# mobileCharger.net
KiCad netlist of a schematic drawn in EAGLE
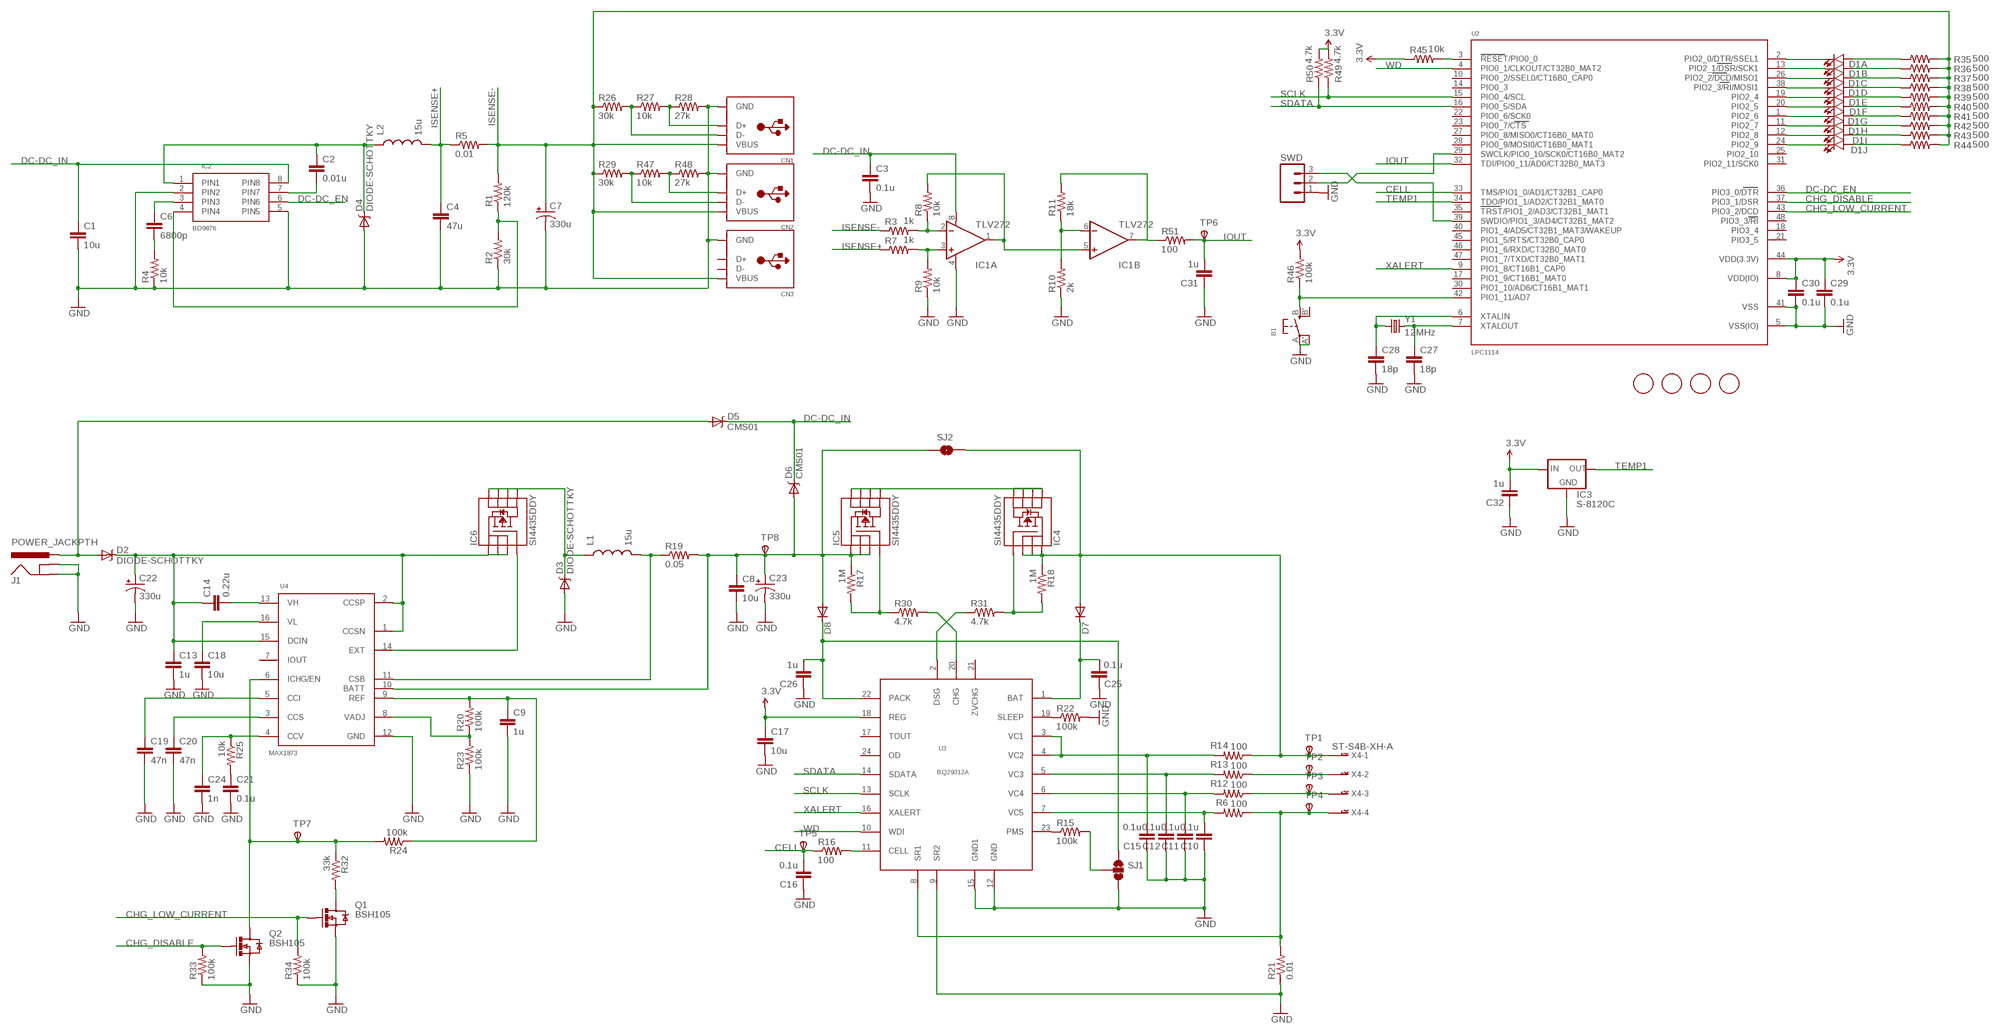
[diagram p0: schematic, sheet 1]

(export (version "E")
  (design (tool "Eeschema 10.0.6"))
  (components
    (comp (ref "B1")
      (value "SWITCH_TACT_SMT")
      (footprint "eagle-import:EVQ-Q2")
      (libsource (lib "eagle-import") (part "SWITCH_TACT_SMT"))
    )
    (comp (ref "C1")
      (value "10u")
      (footprint "eagle-import:0805")
      (libsource (lib "eagle-import") (part "SparkFun-Passives_CAP0805"))
    )
    (comp (ref "C2")
      (value "0.01u")
      (footprint "eagle-import:0603-CAP")
      (libsource (lib "eagle-import") (part "CAP0603-CAP"))
    )
    (comp (ref "C3")
      (value "0.1u")
      (footprint "eagle-import:0603-CAP")
      (libsource (lib "eagle-import") (part "CAP0603-CAP"))
    )
    (comp (ref "C4")
      (value "47u")
      (footprint "eagle-import:1206")
      (libsource (lib "eagle-import") (part "SparkFun-Passives_CAP1206"))
    )
    (comp (ref "C6")
      (value "6800p")
      (footprint "eagle-import:0603-CAP")
      (libsource (lib "eagle-import") (part "CAP0603-CAP"))
    )
    (comp (ref "C7")
      (value "330u")
      (footprint "eagle-import:CPOL-RADIAL-100UF-25V")
      (libsource (lib "eagle-import") (part "CAP_POLPTH1"))
    )
    (comp (ref "C8")
      (value "10u")
      (footprint "eagle-import:0805")
      (libsource (lib "eagle-import") (part "SparkFun-Passives_CAP0805"))
    )
    (comp (ref "C9")
      (value "1u")
      (footprint "eagle-import:0603-CAP")
      (libsource (lib "eagle-import") (part "CAP0603-CAP"))
    )
    (comp (ref "C10")
      (value "0.1u")
      (footprint "eagle-import:0603-CAP")
      (libsource (lib "eagle-import") (part "CAP0603-CAP"))
    )
    (comp (ref "C11")
      (value "0.1u")
      (footprint "eagle-import:0603-CAP")
      (libsource (lib "eagle-import") (part "CAP0603-CAP"))
    )
    (comp (ref "C12")
      (value "0.1u")
      (footprint "eagle-import:0603-CAP")
      (libsource (lib "eagle-import") (part "CAP0603-CAP"))
    )
    (comp (ref "C13")
      (value "1u")
      (footprint "eagle-import:0603-CAP")
      (libsource (lib "eagle-import") (part "CAP0603-CAP"))
    )
    (comp (ref "C14")
      (value "0.22u")
      (footprint "eagle-import:0603-CAP")
      (libsource (lib "eagle-import") (part "CAP0603-CAP"))
    )
    (comp (ref "C15")
      (value "0.1u")
      (footprint "eagle-import:0603-CAP")
      (libsource (lib "eagle-import") (part "CAP0603-CAP"))
    )
    (comp (ref "C16")
      (value "0.1u")
      (footprint "eagle-import:0603-CAP")
      (libsource (lib "eagle-import") (part "CAP0603-CAP"))
    )
    (comp (ref "C17")
      (value "10u")
      (footprint "eagle-import:0805")
      (libsource (lib "eagle-import") (part "SparkFun-Passives_CAP0805"))
    )
    (comp (ref "C18")
      (value "10u")
      (footprint "eagle-import:0805")
      (libsource (lib "eagle-import") (part "SparkFun-Passives_CAP0805"))
    )
    (comp (ref "C19")
      (value "47n")
      (footprint "eagle-import:0603-CAP")
      (libsource (lib "eagle-import") (part "CAP0603-CAP"))
    )
    (comp (ref "C20")
      (value "47n")
      (footprint "eagle-import:0603-CAP")
      (libsource (lib "eagle-import") (part "CAP0603-CAP"))
    )
    (comp (ref "C21")
      (value "0.1u")
      (footprint "eagle-import:0603-CAP")
      (libsource (lib "eagle-import") (part "CAP0603-CAP"))
    )
    (comp (ref "C22")
      (value "330u")
      (footprint "eagle-import:E3,5-8")
      (libsource (lib "eagle-import") (part "CPOL-USE3.5-8"))
    )
    (comp (ref "C23")
      (value "330u")
      (footprint "eagle-import:E3,5-8")
      (libsource (lib "eagle-import") (part "CPOL-USE3.5-8"))
    )
    (comp (ref "C24")
      (value "1n")
      (footprint "eagle-import:0603-CAP")
      (libsource (lib "eagle-import") (part "CAP0603-CAP"))
    )
    (comp (ref "C25")
      (value "0.1u")
      (footprint "eagle-import:0603-CAP")
      (libsource (lib "eagle-import") (part "CAP0603-CAP"))
    )
    (comp (ref "C26")
      (value "1u")
      (footprint "eagle-import:0603-CAP")
      (libsource (lib "eagle-import") (part "CAP0603-CAP"))
    )
    (comp (ref "C27")
      (value "18p")
      (footprint "eagle-import:0603-CAP")
      (libsource (lib "eagle-import") (part "CAP0603-CAP"))
    )
    (comp (ref "C28")
      (value "18p")
      (footprint "eagle-import:0603-CAP")
      (libsource (lib "eagle-import") (part "CAP0603-CAP"))
    )
    (comp (ref "C29")
      (value "0.1u")
      (footprint "eagle-import:0603-CAP")
      (libsource (lib "eagle-import") (part "CAP0603-CAP"))
    )
    (comp (ref "C30")
      (value "0.1u")
      (footprint "eagle-import:0603-CAP")
      (libsource (lib "eagle-import") (part "CAP0603-CAP"))
    )
    (comp (ref "C31")
      (value "1u")
      (footprint "eagle-import:0603-CAP")
      (libsource (lib "eagle-import") (part "CAP0603-CAP"))
    )
    (comp (ref "C32")
      (value "1u")
      (footprint "eagle-import:0603-CAP")
      (libsource (lib "eagle-import") (part "CAP0603-CAP"))
    )
    (comp (ref "CN1")
      (value "USB_TYPEAPTHFML")
      (footprint "eagle-import:USB_HOST-PTH")
      (libsource (lib "eagle-import") (part "USB_TYPEAPTHFML"))
    )
    (comp (ref "CN2")
      (value "USB_TYPEAPTHFML")
      (footprint "eagle-import:USB_HOST-PTH")
      (libsource (lib "eagle-import") (part "USB_TYPEAPTHFML"))
    )
    (comp (ref "CN3")
      (value "USB_TYPEAPTHFML")
      (footprint "eagle-import:USB_HOST-PTH")
      (libsource (lib "eagle-import") (part "USB_TYPEAPTHFML"))
    )
    (comp (ref "D1")
      (value "LED_BARGRAPH_10")
      (footprint "eagle-import:LED_BARGAPH_10")
      (libsource (lib "eagle-import") (part "LED_BARGRAPH_10"))
    )
    (comp (ref "D2")
      (value "DIODE-SCHOTTKY")
      (footprint "eagle-import:SOD-128")
      (libsource (lib "eagle-import") (part "DIODE-SCHOTTKY"))
    )
    (comp (ref "D3")
      (value "DIODE-SCHOTTKY")
      (footprint "eagle-import:SOD-128")
      (libsource (lib "eagle-import") (part "DIODE-SCHOTTKY"))
    )
    (comp (ref "D4")
      (value "DIODE-SCHOTTKY")
      (footprint "eagle-import:SOD-128")
      (libsource (lib "eagle-import") (part "DIODE-SCHOTTKY"))
    )
    (comp (ref "D5")
      (value "CMS01")
      (footprint "eagle-import:M-FLAT")
      (libsource (lib "eagle-import") (part "CMS01"))
    )
    (comp (ref "D6")
      (value "CMS01")
      (footprint "eagle-import:M-FLAT")
      (libsource (lib "eagle-import") (part "CMS01"))
    )
    (comp (ref "D7")
      (value "DIODESOD523")
      (footprint "eagle-import:SOD523")
      (libsource (lib "eagle-import") (part "DIODESOD523"))
    )
    (comp (ref "D8")
      (value "DIODESOD523")
      (footprint "eagle-import:SOD523")
      (libsource (lib "eagle-import") (part "DIODESOD523"))
    )
    (comp (ref "IC1")
      (value "TLV272")
      (footprint "eagle-import:SO08")
      (libsource (lib "eagle-import") (part "OPAMP-DUALU"))
    )
    (comp (ref "IC2")
      (value "BD9876")
      (footprint "eagle-import:SO08")
      (libsource (lib "eagle-import") (part "SOT8"))
    )
    (comp (ref "IC3")
      (value "S-8120C")
      (footprint "eagle-import:SC-82AB")
      (libsource (lib "eagle-import") (part "S-8120C"))
    )
    (comp (ref "IC4")
      (value "SI4435DDY")
      (footprint "eagle-import:SO08")
      (libsource (lib "eagle-import") (part "MOSFET-PCHANNEL-SOIC8SOIC8"))
    )
    (comp (ref "IC5")
      (value "SI4435DDY")
      (footprint "eagle-import:SO08")
      (libsource (lib "eagle-import") (part "MOSFET-PCHANNEL-SOIC8SOIC8"))
    )
    (comp (ref "IC6")
      (value "SI4435DDY")
      (footprint "eagle-import:SO08")
      (libsource (lib "eagle-import") (part "MOSFET-PCHANNEL-SOIC8SOIC8"))
    )
    (comp (ref "J1")
      (value "POWER_JACKPTH")
      (footprint "eagle-import:POWER_JACK_PTH")
      (libsource (lib "eagle-import") (part "POWER_JACKPTH"))
    )
    (comp (ref "L1")
      (value "15u")
      (footprint "eagle-import:CDRH125")
      (libsource (lib "eagle-import") (part "INDUCTORPWR"))
    )
    (comp (ref "L2")
      (value "15u")
      (footprint "eagle-import:CDRH125")
      (libsource (lib "eagle-import") (part "INDUCTORPWR"))
    )
    (comp (ref "Q1")
      (value "BSH105")
      (footprint "eagle-import:SOT23-3")
      (libsource (lib "eagle-import") (part "MOSFET-NCHANNELSMD"))
    )
    (comp (ref "Q2")
      (value "BSH105")
      (footprint "eagle-import:SOT23-3")
      (libsource (lib "eagle-import") (part "MOSFET-NCHANNELSMD"))
    )
    (comp (ref "R1")
      (value "120k")
      (footprint "eagle-import:0603-RES")
      (libsource (lib "eagle-import") (part "RESISTOR0603-RES"))
    )
    (comp (ref "R2")
      (value "30k")
      (footprint "eagle-import:0603-RES")
      (libsource (lib "eagle-import") (part "RESISTOR0603-RES"))
    )
    (comp (ref "R3")
      (value "1k")
      (footprint "eagle-import:0603-RES")
      (libsource (lib "eagle-import") (part "RESISTOR0603-RES"))
    )
    (comp (ref "R4")
      (value "10k")
      (footprint "eagle-import:0603-RES")
      (libsource (lib "eagle-import") (part "SparkFun-Passives_RESISTOR0603-RES"))
    )
    (comp (ref "R5")
      (value "0.01")
      (footprint "eagle-import:R1206")
      (libsource (lib "eagle-import") (part "R-US_R1206"))
    )
    (comp (ref "R6")
      (value "100")
      (footprint "eagle-import:0603-RES")
      (libsource (lib "eagle-import") (part "RESISTOR0603-RES"))
    )
    (comp (ref "R7")
      (value "1k")
      (footprint "eagle-import:0603-RES")
      (libsource (lib "eagle-import") (part "RESISTOR0603-RES"))
    )
    (comp (ref "R8")
      (value "10k")
      (footprint "eagle-import:0603-RES")
      (libsource (lib "eagle-import") (part "RESISTOR0603-RES"))
    )
    (comp (ref "R9")
      (value "10k")
      (footprint "eagle-import:0603-RES")
      (libsource (lib "eagle-import") (part "RESISTOR0603-RES"))
    )
    (comp (ref "R10")
      (value "2k")
      (footprint "eagle-import:0603-RES")
      (libsource (lib "eagle-import") (part "RESISTOR0603-RES"))
    )
    (comp (ref "R11")
      (value "18k")
      (footprint "eagle-import:0603-RES")
      (libsource (lib "eagle-import") (part "RESISTOR0603-RES"))
    )
    (comp (ref "R12")
      (value "100")
      (footprint "eagle-import:0603-RES")
      (libsource (lib "eagle-import") (part "RESISTOR0603-RES"))
    )
    (comp (ref "R13")
      (value "100")
      (footprint "eagle-import:0603-RES")
      (libsource (lib "eagle-import") (part "RESISTOR0603-RES"))
    )
    (comp (ref "R14")
      (value "100")
      (footprint "eagle-import:0603-RES")
      (libsource (lib "eagle-import") (part "RESISTOR0603-RES"))
    )
    (comp (ref "R15")
      (value "100k")
      (footprint "eagle-import:0603-RES")
      (libsource (lib "eagle-import") (part "RESISTOR0603-RES"))
    )
    (comp (ref "R16")
      (value "100")
      (footprint "eagle-import:0603-RES")
      (libsource (lib "eagle-import") (part "RESISTOR0603-RES"))
    )
    (comp (ref "R17")
      (value "1M")
      (footprint "eagle-import:0603-RES")
      (libsource (lib "eagle-import") (part "RESISTOR0603-RES"))
    )
    (comp (ref "R18")
      (value "1M")
      (footprint "eagle-import:0603-RES")
      (libsource (lib "eagle-import") (part "RESISTOR0603-RES"))
    )
    (comp (ref "R19")
      (value "0.05")
      (footprint "eagle-import:R2512")
      (libsource (lib "eagle-import") (part "resistor_R-US_R2512"))
    )
    (comp (ref "R20")
      (value "100k")
      (footprint "eagle-import:0603-RES")
      (libsource (lib "eagle-import") (part "RESISTOR0603-RES"))
    )
    (comp (ref "R21")
      (value "0.01")
      (footprint "eagle-import:R1206")
      (libsource (lib "eagle-import") (part "R-US_R1206"))
    )
    (comp (ref "R22")
      (value "100k")
      (footprint "eagle-import:0603-RES")
      (libsource (lib "eagle-import") (part "RESISTOR0603-RES"))
    )
    (comp (ref "R23")
      (value "100k")
      (footprint "eagle-import:0603-RES")
      (libsource (lib "eagle-import") (part "RESISTOR0603-RES"))
    )
    (comp (ref "R24")
      (value "100k")
      (footprint "eagle-import:0603-RES")
      (libsource (lib "eagle-import") (part "RESISTOR0603-RES"))
    )
    (comp (ref "R25")
      (value "10k")
      (footprint "eagle-import:0603-RES")
      (libsource (lib "eagle-import") (part "RESISTOR0603-RES"))
    )
    (comp (ref "R26")
      (value "30k")
      (footprint "eagle-import:0603-RES")
      (libsource (lib "eagle-import") (part "RESISTOR0603-RES"))
    )
    (comp (ref "R27")
      (value "10k")
      (footprint "eagle-import:0603-RES")
      (libsource (lib "eagle-import") (part "RESISTOR0603-RES"))
    )
    (comp (ref "R28")
      (value "27k")
      (footprint "eagle-import:0603-RES")
      (libsource (lib "eagle-import") (part "RESISTOR0603-RES"))
    )
    (comp (ref "R29")
      (value "30k")
      (footprint "eagle-import:0603-RES")
      (libsource (lib "eagle-import") (part "RESISTOR0603-RES"))
    )
    (comp (ref "R30")
      (value "4.7k")
      (footprint "eagle-import:0603-RES")
      (libsource (lib "eagle-import") (part "RESISTOR0603-RES"))
    )
    (comp (ref "R31")
      (value "4.7k")
      (footprint "eagle-import:0603-RES")
      (libsource (lib "eagle-import") (part "RESISTOR0603-RES"))
    )
    (comp (ref "R32")
      (value "33k")
      (footprint "eagle-import:0603-RES")
      (libsource (lib "eagle-import") (part "RESISTOR0603-RES"))
    )
    (comp (ref "R33")
      (value "100k")
      (footprint "eagle-import:0603-RES")
      (libsource (lib "eagle-import") (part "RESISTOR0603-RES"))
    )
    (comp (ref "R34")
      (value "100k")
      (footprint "eagle-import:0603-RES")
      (libsource (lib "eagle-import") (part "RESISTOR0603-RES"))
    )
    (comp (ref "R35")
      (value "500")
      (footprint "eagle-import:0603-RES")
      (libsource (lib "eagle-import") (part "RESISTOR0603-RES"))
    )
    (comp (ref "R36")
      (value "500")
      (footprint "eagle-import:0603-RES")
      (libsource (lib "eagle-import") (part "RESISTOR0603-RES"))
    )
    (comp (ref "R37")
      (value "500")
      (footprint "eagle-import:0603-RES")
      (libsource (lib "eagle-import") (part "RESISTOR0603-RES"))
    )
    (comp (ref "R38")
      (value "500")
      (footprint "eagle-import:0603-RES")
      (libsource (lib "eagle-import") (part "RESISTOR0603-RES"))
    )
    (comp (ref "R39")
      (value "500")
      (footprint "eagle-import:0603-RES")
      (libsource (lib "eagle-import") (part "RESISTOR0603-RES"))
    )
    (comp (ref "R40")
      (value "500")
      (footprint "eagle-import:0603-RES")
      (libsource (lib "eagle-import") (part "RESISTOR0603-RES"))
    )
    (comp (ref "R41")
      (value "500")
      (footprint "eagle-import:0603-RES")
      (libsource (lib "eagle-import") (part "RESISTOR0603-RES"))
    )
    (comp (ref "R42")
      (value "500")
      (footprint "eagle-import:0603-RES")
      (libsource (lib "eagle-import") (part "RESISTOR0603-RES"))
    )
    (comp (ref "R43")
      (value "500")
      (footprint "eagle-import:0603-RES")
      (libsource (lib "eagle-import") (part "RESISTOR0603-RES"))
    )
    (comp (ref "R44")
      (value "500")
      (footprint "eagle-import:0603-RES")
      (libsource (lib "eagle-import") (part "RESISTOR0603-RES"))
    )
    (comp (ref "R45")
      (value "10k")
      (footprint "eagle-import:0603-RES")
      (libsource (lib "eagle-import") (part "RESISTOR0603-RES"))
    )
    (comp (ref "R46")
      (value "100k")
      (footprint "eagle-import:0603-RES")
      (libsource (lib "eagle-import") (part "RESISTOR0603-RES"))
    )
    (comp (ref "R47")
      (value "10k")
      (footprint "eagle-import:0603-RES")
      (libsource (lib "eagle-import") (part "RESISTOR0603-RES"))
    )
    (comp (ref "R48")
      (value "27k")
      (footprint "eagle-import:0603-RES")
      (libsource (lib "eagle-import") (part "RESISTOR0603-RES"))
    )
    (comp (ref "R49")
      (value "4.7k")
      (footprint "eagle-import:0603-RES")
      (libsource (lib "eagle-import") (part "RESISTOR0603-RES"))
    )
    (comp (ref "R50")
      (value "4.7k")
      (footprint "eagle-import:0603-RES")
      (libsource (lib "eagle-import") (part "RESISTOR0603-RES"))
    )
    (comp (ref "R51")
      (value "100")
      (footprint "eagle-import:0603-RES")
      (libsource (lib "eagle-import") (part "RESISTOR0603-RES"))
    )
    (comp (ref "SJ1")
      (value "SOLDERJUMPER_2WAYT")
      (footprint "eagle-import:SJ_2")
      (libsource (lib "eagle-import") (part "SOLDERJUMPER_2WAYT"))
    )
    (comp (ref "SJ2")
      (value "SOLDERJUMPERNO")
      (footprint "eagle-import:SJ_2S-NO")
      (libsource (lib "eagle-import") (part "SOLDERJUMPERNO"))
    )
    (comp (ref "SWD")
      (value "M03PTH")
      (footprint "eagle-import:1X03")
      (libsource (lib "eagle-import") (part "M03PTH"))
    )
    (comp (ref "TP1")
      (value "TPSPAD1-13")
      (footprint "eagle-import:P1-13")
      (libsource (lib "eagle-import") (part "TPSPAD1-13"))
    )
    (comp (ref "TP2")
      (value "TPSPAD1-13")
      (footprint "eagle-import:P1-13")
      (libsource (lib "eagle-import") (part "TPSPAD1-13"))
    )
    (comp (ref "TP3")
      (value "TPSPAD1-13")
      (footprint "eagle-import:P1-13")
      (libsource (lib "eagle-import") (part "TPSPAD1-13"))
    )
    (comp (ref "TP4")
      (value "TPSPAD1-13")
      (footprint "eagle-import:P1-13")
      (libsource (lib "eagle-import") (part "TPSPAD1-13"))
    )
    (comp (ref "TP5")
      (value "TPSPAD1-13")
      (footprint "eagle-import:P1-13")
      (libsource (lib "eagle-import") (part "TPSPAD1-13"))
    )
    (comp (ref "TP6")
      (value "TPSPAD1-13")
      (footprint "eagle-import:P1-13")
      (libsource (lib "eagle-import") (part "TPSPAD1-13"))
    )
    (comp (ref "TP7")
      (value "TPSPAD1-13")
      (footprint "eagle-import:P1-13")
      (libsource (lib "eagle-import") (part "TPSPAD1-13"))
    )
    (comp (ref "TP8")
      (value "TPSPAD1-13")
      (footprint "eagle-import:P1-13")
      (libsource (lib "eagle-import") (part "TPSPAD1-13"))
    )
    (comp (ref "U$1")
      (value "MOUNTINGHOLE2.0")
      (footprint "eagle-import:MOUNTINGHOLE_2.0_PLATED")
      (libsource (lib "eagle-import") (part "MOUNTINGHOLE2.0"))
    )
    (comp (ref "U$2")
      (value "MOUNTINGHOLE2.0")
      (footprint "eagle-import:MOUNTINGHOLE_2.0_PLATED")
      (libsource (lib "eagle-import") (part "MOUNTINGHOLE2.0"))
    )
    (comp (ref "U$3")
      (value "MOUNTINGHOLE2.0")
      (footprint "eagle-import:MOUNTINGHOLE_2.0_PLATED")
      (libsource (lib "eagle-import") (part "MOUNTINGHOLE2.0"))
    )
    (comp (ref "U$7")
      (value "MOUNTINGHOLE2.0")
      (footprint "eagle-import:MOUNTINGHOLE_2.0_PLATED")
      (libsource (lib "eagle-import") (part "MOUNTINGHOLE2.0"))
    )
    (comp (ref "U2")
      (value "LPC1114")
      (footprint "eagle-import:LQFP48")
      (fields (field (name "MANF") "NXP"))
      (libsource (lib "eagle-import") (part "LPC1113/4"))
    )
    (comp (ref "U3")
      (value "BQ29312A")
      (footprint "eagle-import:TSSOP-24")
      (libsource (lib "eagle-import") (part "BQ29312A"))
    )
    (comp (ref "U4")
      (value "MAX1873")
      (footprint "eagle-import:TSSOP16")
      (libsource (lib "eagle-import") (part "MAX1873"))
    )
    (comp (ref "X4")
      (value "ST-S4B-XH-A")
      (footprint "eagle-import:B4B-XH")
      (libsource (lib "eagle-import") (part "04-JST-B4B-XH-A"))
    )
    (comp (ref "Y1")
      (value "12MHz")
      (footprint "eagle-import:HC49UP")
      (libsource (lib "eagle-import") (part "CRYSTALSMD"))
    )
  )
  (nets
    (net (code "1") (name "/CELL") (class "Default")
      (node (ref "C16") (pin "2") (pinfunction "2_2") (pintype "passive"))
      (node (ref "R16") (pin "1") (pinfunction "1_1") (pintype "passive"))
      (node (ref "TP5") (pin "TP") (pinfunction "PP_TP") (pintype "input"))
      (node (ref "U2") (pin "33") (pinfunction "TMS/PIO1_0/AD1/CT32B1_CAP0_33") (pintype "bidirectional"))
    )
    (net (code "2") (name "/CHG_DISABLE") (class "Default")
      (node (ref "Q2") (pin "1") (pinfunction "G_1") (pintype "passive"))
      (node (ref "R33") (pin "2") (pinfunction "2_2") (pintype "passive"))
      (node (ref "U2") (pin "37") (pinfunction "PIO3_1/DSR_37") (pintype "bidirectional"))
    )
    (net (code "3") (name "/CHG_LOW_CURRENT") (class "Default")
      (node (ref "Q1") (pin "1") (pinfunction "G_1") (pintype "passive"))
      (node (ref "R34") (pin "2") (pinfunction "2_2") (pintype "passive"))
      (node (ref "U2") (pin "43") (pinfunction "PIO3_2/DCD_43") (pintype "bidirectional"))
    )
    (net (code "4") (name "/DC-DC_EN") (class "Default")
      (node (ref "IC2") (pin "6") (pinfunction "PIN6_6") (pintype "bidirectional"))
      (node (ref "U2") (pin "36") (pinfunction "PIO3_0/DTR_36") (pintype "bidirectional"))
    )
    (net (code "5") (name "/DC-DC_IN") (class "Default")
      (node (ref "C1") (pin "1") (pinfunction "1_1") (pintype "passive"))
      (node (ref "C3") (pin "1") (pinfunction "1_1") (pintype "passive"))
      (node (ref "D5") (pin "P$2") (pinfunction "C_P$2") (pintype "passive"))
      (node (ref "D6") (pin "P$2") (pinfunction "C_P$2") (pintype "passive"))
      (node (ref "IC1") (pin "8") (pinfunction "V+_8") (pintype "power_in"))
      (node (ref "IC2") (pin "8") (pinfunction "PIN8_8") (pintype "bidirectional"))
    )
    (net (code "6") (name "/IOUT") (class "Default")
      (node (ref "C31") (pin "2") (pinfunction "2_2") (pintype "passive"))
      (node (ref "R51") (pin "2") (pinfunction "2_2") (pintype "passive"))
      (node (ref "TP6") (pin "TP") (pinfunction "PP_TP") (pintype "input"))
      (node (ref "U2") (pin "32") (pinfunction "TDI/PIO0_11/AD0/CT32B0_MAT3_32") (pintype "bidirectional"))
    )
    (net (code "7") (name "/ISENSE+") (class "Default")
      (node (ref "C4") (pin "1") (pinfunction "1_1") (pintype "passive"))
      (node (ref "L2") (pin "2") (pinfunction "2_2") (pintype "passive"))
      (node (ref "R5") (pin "1") (pinfunction "1_1") (pintype "passive"))
      (node (ref "R7") (pin "1") (pinfunction "1_1") (pintype "passive"))
    )
    (net (code "8") (name "/ISENSE-") (class "Default")
      (node (ref "C7") (pin "1") (pinfunction "+_1") (pintype "passive"))
      (node (ref "CN1") (pin "VBUS") (pinfunction "VBUS_VBUS") (pintype "power_in"))
      (node (ref "CN2") (pin "VBUS") (pinfunction "VBUS_VBUS") (pintype "power_in"))
      (node (ref "CN3") (pin "VBUS") (pinfunction "VBUS_VBUS") (pintype "power_in"))
      (node (ref "R1") (pin "2") (pinfunction "2_2") (pintype "passive"))
      (node (ref "R26") (pin "1") (pinfunction "1_1") (pintype "passive"))
      (node (ref "R29") (pin "1") (pinfunction "1_1") (pintype "passive"))
      (node (ref "R3") (pin "1") (pinfunction "1_1") (pintype "passive"))
      (node (ref "R35") (pin "2") (pinfunction "2_2") (pintype "passive"))
      (node (ref "R36") (pin "2") (pinfunction "2_2") (pintype "passive"))
      (node (ref "R37") (pin "2") (pinfunction "2_2") (pintype "passive"))
      (node (ref "R38") (pin "2") (pinfunction "2_2") (pintype "passive"))
      (node (ref "R39") (pin "2") (pinfunction "2_2") (pintype "passive"))
      (node (ref "R40") (pin "2") (pinfunction "2_2") (pintype "passive"))
      (node (ref "R41") (pin "2") (pinfunction "2_2") (pintype "passive"))
      (node (ref "R42") (pin "2") (pinfunction "2_2") (pintype "passive"))
      (node (ref "R43") (pin "2") (pinfunction "2_2") (pintype "passive"))
      (node (ref "R44") (pin "2") (pinfunction "2_2") (pintype "passive"))
      (node (ref "R5") (pin "2") (pinfunction "2_2") (pintype "passive"))
    )
    (net (code "9") (name "/SCLK") (class "Default")
      (node (ref "R49") (pin "1") (pinfunction "1_1") (pintype "passive"))
      (node (ref "U2") (pin "15") (pinfunction "PIO0_4/SCL_15") (pintype "bidirectional"))
      (node (ref "U3") (pin "13") (pinfunction "SCLK_13") (pintype "bidirectional"))
    )
    (net (code "10") (name "/SDATA") (class "Default")
      (node (ref "R50") (pin "1") (pinfunction "1_1") (pintype "passive"))
      (node (ref "U2") (pin "16") (pinfunction "PIO0_5/SDA_16") (pintype "bidirectional"))
      (node (ref "U3") (pin "14") (pinfunction "SDATA_14") (pintype "bidirectional"))
    )
    (net (code "11") (name "/TEMP1") (class "Default")
      (node (ref "IC3") (pin "P$4") (pinfunction "OUT_P$4") (pintype "output"))
      (node (ref "U2") (pin "34") (pinfunction "TDO/PIO1_1/AD2/CT32B1_MAT0_34") (pintype "bidirectional"))
    )
    (net (code "12") (name "/WD") (class "Default")
      (node (ref "U2") (pin "4") (pinfunction "PIO0_1/CLKOUT/CT32B0_MAT2_4") (pintype "bidirectional"))
      (node (ref "U3") (pin "10") (pinfunction "WDI_10") (pintype "bidirectional"))
    )
    (net (code "13") (name "/XALERT") (class "Default")
      (node (ref "U2") (pin "9") (pinfunction "PIO1_8/CT16B1_CAP0_9") (pintype "bidirectional"))
      (node (ref "U3") (pin "16") (pinfunction "XALERT_16") (pintype "bidirectional"))
    )
    (net (code "14") (name "3.3V") (class "Default")
      (node (ref "C17") (pin "1") (pinfunction "1_1") (pintype "passive"))
      (node (ref "C29") (pin "1") (pinfunction "1_1") (pintype "passive"))
      (node (ref "C30") (pin "1") (pinfunction "1_1") (pintype "passive"))
      (node (ref "C32") (pin "2") (pinfunction "2_2") (pintype "passive"))
      (node (ref "IC3") (pin "P$1") (pinfunction "IN_P$1") (pintype "input"))
      (node (ref "R45") (pin "1") (pinfunction "1_1") (pintype "passive"))
      (node (ref "R46") (pin "2") (pinfunction "2_2") (pintype "passive"))
      (node (ref "R49") (pin "2") (pinfunction "2_2") (pintype "passive"))
      (node (ref "R50") (pin "2") (pinfunction "2_2") (pintype "passive"))
      (node (ref "U2") (pin "44") (pinfunction "VDD(3.3V)_44") (pintype "power_in"))
      (node (ref "U2") (pin "8") (pinfunction "VDD(IO)_8") (pintype "power_in"))
      (node (ref "U3") (pin "18") (pinfunction "REG_18") (pintype "bidirectional"))
    )
    (net (code "15") (name "GND") (class "Default")
      (node (ref "B1") (pin "A") (pinfunction "P_A") (pintype "passive"))
      (node (ref "B1") (pin "A'") (pinfunction "P1_A'") (pintype "passive"))
      (node (ref "C1") (pin "2") (pinfunction "2_2") (pintype "passive"))
      (node (ref "C10") (pin "1") (pinfunction "1_1") (pintype "passive"))
      (node (ref "C11") (pin "1") (pinfunction "1_1") (pintype "passive"))
      (node (ref "C12") (pin "1") (pinfunction "1_1") (pintype "passive"))
      (node (ref "C13") (pin "2") (pinfunction "2_2") (pintype "passive"))
      (node (ref "C15") (pin "1") (pinfunction "1_1") (pintype "passive"))
      (node (ref "C16") (pin "1") (pinfunction "1_1") (pintype "passive"))
      (node (ref "C17") (pin "2") (pinfunction "2_2") (pintype "passive"))
      (node (ref "C18") (pin "2") (pinfunction "2_2") (pintype "passive"))
      (node (ref "C19") (pin "2") (pinfunction "2_2") (pintype "passive"))
      (node (ref "C20") (pin "2") (pinfunction "2_2") (pintype "passive"))
      (node (ref "C21") (pin "2") (pinfunction "2_2") (pintype "passive"))
      (node (ref "C22") (pin "-") (pinfunction "-_-") (pintype "passive"))
      (node (ref "C23") (pin "-") (pinfunction "-_-") (pintype "passive"))
      (node (ref "C24") (pin "2") (pinfunction "2_2") (pintype "passive"))
      (node (ref "C25") (pin "1") (pinfunction "1_1") (pintype "passive"))
      (node (ref "C26") (pin "1") (pinfunction "1_1") (pintype "passive"))
      (node (ref "C27") (pin "2") (pinfunction "2_2") (pintype "passive"))
      (node (ref "C28") (pin "2") (pinfunction "2_2") (pintype "passive"))
      (node (ref "C29") (pin "2") (pinfunction "2_2") (pintype "passive"))
      (node (ref "C3") (pin "2") (pinfunction "2_2") (pintype "passive"))
      (node (ref "C30") (pin "2") (pinfunction "2_2") (pintype "passive"))
      (node (ref "C31") (pin "1") (pinfunction "1_1") (pintype "passive"))
      (node (ref "C32") (pin "1") (pinfunction "1_1") (pintype "passive"))
      (node (ref "C4") (pin "2") (pinfunction "2_2") (pintype "passive"))
      (node (ref "C7") (pin "2") (pinfunction "-_2") (pintype "passive"))
      (node (ref "C8") (pin "2") (pinfunction "2_2") (pintype "passive"))
      (node (ref "C9") (pin "2") (pinfunction "2_2") (pintype "passive"))
      (node (ref "CN1") (pin "GND") (pinfunction "GND_GND") (pintype "power_in"))
      (node (ref "CN2") (pin "GND") (pinfunction "GND_GND") (pintype "power_in"))
      (node (ref "CN3") (pin "GND") (pinfunction "GND_GND") (pintype "power_in"))
      (node (ref "D3") (pin "P$1") (pinfunction "A_P$1") (pintype "passive"))
      (node (ref "D4") (pin "P$1") (pinfunction "A_P$1") (pintype "passive"))
      (node (ref "IC1") (pin "4") (pinfunction "V-_4") (pintype "power_in"))
      (node (ref "IC2") (pin "2") (pinfunction "PIN2_2") (pintype "bidirectional"))
      (node (ref "IC2") (pin "5") (pinfunction "PIN5_5") (pintype "bidirectional"))
      (node (ref "IC3") (pin "P$2") (pinfunction "GND_P$2") (pintype "input"))
      (node (ref "J1") (pin "GND") (pinfunction "GND_GND") (pintype "bidirectional"))
      (node (ref "J1") (pin "GNDBREAK") (pinfunction "GNDBREAK_GNDBREAK") (pintype "bidirectional"))
      (node (ref "Q1") (pin "2") (pinfunction "S_2") (pintype "passive"))
      (node (ref "Q2") (pin "2") (pinfunction "S_2") (pintype "passive"))
      (node (ref "R10") (pin "1") (pinfunction "1_1") (pintype "passive"))
      (node (ref "R2") (pin "1") (pinfunction "1_1") (pintype "passive"))
      (node (ref "R21") (pin "1") (pinfunction "1_1") (pintype "passive"))
      (node (ref "R22") (pin "2") (pinfunction "2_2") (pintype "passive"))
      (node (ref "R23") (pin "1") (pinfunction "1_1") (pintype "passive"))
      (node (ref "R28") (pin "2") (pinfunction "2_2") (pintype "passive"))
      (node (ref "R33") (pin "1") (pinfunction "1_1") (pintype "passive"))
      (node (ref "R34") (pin "1") (pinfunction "1_1") (pintype "passive"))
      (node (ref "R4") (pin "1") (pinfunction "1_1") (pintype "passive"))
      (node (ref "R48") (pin "2") (pinfunction "2_2") (pintype "passive"))
      (node (ref "R9") (pin "1") (pinfunction "1_1") (pintype "passive"))
      (node (ref "SJ1") (pin "3") (pinfunction "3_3") (pintype "passive"))
      (node (ref "SWD") (pin "1") (pinfunction "1_1") (pintype "passive"))
      (node (ref "U2") (pin "41") (pinfunction "VSS_41") (pintype "power_in"))
      (node (ref "U2") (pin "5") (pinfunction "VSS(IO)_5") (pintype "power_in"))
      (node (ref "U3") (pin "12") (pinfunction "GND_12") (pintype "bidirectional"))
      (node (ref "U3") (pin "15") (pinfunction "GND1_15") (pintype "bidirectional"))
      (node (ref "U3") (pin "9") (pinfunction "SR2_9") (pintype "bidirectional"))
      (node (ref "U4") (pin "12") (pinfunction "GND_12") (pintype "bidirectional"))
    )
    (net (code "16") (name "Net-(B1-S)") (class "Default")
      (node (ref "B1") (pin "B") (pinfunction "S_B") (pintype "passive"))
      (node (ref "R46") (pin "1") (pinfunction "1_1") (pintype "passive"))
      (node (ref "U2") (pin "42") (pinfunction "PIO1_11/AD7_42") (pintype "bidirectional"))
    )
    (net (code "17") (name "Net-(C6-Pad2)") (class "Default")
      (node (ref "C6") (pin "2") (pinfunction "2_2") (pintype "passive"))
      (node (ref "R4") (pin "2") (pinfunction "2_2") (pintype "passive"))
    )
    (net (code "18") (name "Net-(C21-Pad1)") (class "Default")
      (node (ref "C21") (pin "1") (pinfunction "1_1") (pintype "passive"))
      (node (ref "R25") (pin "2") (pinfunction "2_2") (pintype "passive"))
    )
    (net (code "19") (name "Net-(CN1-PadD+)") (class "Default")
      (node (ref "CN1") (pin "D+") (pinfunction "D+_D+") (pintype "bidirectional"))
      (node (ref "R27") (pin "2") (pinfunction "2_2") (pintype "passive"))
      (node (ref "R28") (pin "1") (pinfunction "1_1") (pintype "passive"))
    )
    (net (code "20") (name "Net-(CN1-PadD-)") (class "Default")
      (node (ref "CN1") (pin "D-") (pinfunction "D-_D-") (pintype "bidirectional"))
      (node (ref "R26") (pin "2") (pinfunction "2_2") (pintype "passive"))
      (node (ref "R27") (pin "1") (pinfunction "1_1") (pintype "passive"))
    )
    (net (code "21") (name "Net-(CN2-PadD+)") (class "Default")
      (node (ref "CN2") (pin "D+") (pinfunction "D+_D+") (pintype "bidirectional"))
      (node (ref "R47") (pin "2") (pinfunction "2_2") (pintype "passive"))
      (node (ref "R48") (pin "1") (pinfunction "1_1") (pintype "passive"))
    )
    (net (code "22") (name "Net-(CN2-PadD-)") (class "Default")
      (node (ref "CN2") (pin "D-") (pinfunction "D-_D-") (pintype "bidirectional"))
      (node (ref "R29") (pin "2") (pinfunction "2_2") (pintype "passive"))
      (node (ref "R47") (pin "1") (pinfunction "1_1") (pintype "passive"))
    )
    (net (code "23") (name "Net-(D1A-A)") (class "Default")
      (node (ref "D1") (pin "1") (pinfunction "A_1") (pintype "passive"))
      (node (ref "R35") (pin "1") (pinfunction "1_1") (pintype "passive"))
    )
    (net (code "24") (name "Net-(D1A-C)") (class "Default")
      (node (ref "D1") (pin "20") (pinfunction "C_20") (pintype "passive"))
      (node (ref "U2") (pin "2") (pinfunction "PIO2_0/DTR/SSEL1_2") (pintype "bidirectional"))
    )
    (net (code "25") (name "Net-(D1B-A)") (class "Default")
      (node (ref "D1") (pin "2") (pinfunction "A_2") (pintype "passive"))
      (node (ref "R36") (pin "1") (pinfunction "1_1") (pintype "passive"))
    )
    (net (code "26") (name "Net-(D1B-C)") (class "Default")
      (node (ref "D1") (pin "19") (pinfunction "C_19") (pintype "passive"))
      (node (ref "U2") (pin "13") (pinfunction "PIO2_1/DSR/SCK1_13") (pintype "bidirectional"))
    )
    (net (code "27") (name "Net-(D1C-A)") (class "Default")
      (node (ref "D1") (pin "3") (pinfunction "A_3") (pintype "passive"))
      (node (ref "R37") (pin "1") (pinfunction "1_1") (pintype "passive"))
    )
    (net (code "28") (name "Net-(D1C-C)") (class "Default")
      (node (ref "D1") (pin "18") (pinfunction "C_18") (pintype "passive"))
      (node (ref "U2") (pin "26") (pinfunction "PIO2_2/DCD/MISO1_26") (pintype "bidirectional"))
    )
    (net (code "29") (name "Net-(D1D-A)") (class "Default")
      (node (ref "D1") (pin "4") (pinfunction "A_4") (pintype "passive"))
      (node (ref "R38") (pin "1") (pinfunction "1_1") (pintype "passive"))
    )
    (net (code "30") (name "Net-(D1D-C)") (class "Default")
      (node (ref "D1") (pin "17") (pinfunction "C_17") (pintype "passive"))
      (node (ref "U2") (pin "38") (pinfunction "PIO2_3/RI/MOSI1_38") (pintype "bidirectional"))
    )
    (net (code "31") (name "Net-(D1E-A)") (class "Default")
      (node (ref "D1") (pin "5") (pinfunction "A_5") (pintype "passive"))
      (node (ref "R39") (pin "1") (pinfunction "1_1") (pintype "passive"))
    )
    (net (code "32") (name "Net-(D1E-C)") (class "Default")
      (node (ref "D1") (pin "16") (pinfunction "C_16") (pintype "passive"))
      (node (ref "U2") (pin "19") (pinfunction "PIO2_4_19") (pintype "bidirectional"))
    )
    (net (code "33") (name "Net-(D1F-A)") (class "Default")
      (node (ref "D1") (pin "6") (pinfunction "A_6") (pintype "passive"))
      (node (ref "R40") (pin "1") (pinfunction "1_1") (pintype "passive"))
    )
    (net (code "34") (name "Net-(D1F-C)") (class "Default")
      (node (ref "D1") (pin "15") (pinfunction "C_15") (pintype "passive"))
      (node (ref "U2") (pin "20") (pinfunction "PIO2_5_20") (pintype "bidirectional"))
    )
    (net (code "35") (name "Net-(D1G-A)") (class "Default")
      (node (ref "D1") (pin "7") (pinfunction "A_7") (pintype "passive"))
      (node (ref "R41") (pin "1") (pinfunction "1_1") (pintype "passive"))
    )
    (net (code "36") (name "Net-(D1G-C)") (class "Default")
      (node (ref "D1") (pin "14") (pinfunction "C_14") (pintype "passive"))
      (node (ref "U2") (pin "1") (pinfunction "PIO2_6_1") (pintype "bidirectional"))
    )
    (net (code "37") (name "Net-(D1H-A)") (class "Default")
      (node (ref "D1") (pin "8") (pinfunction "A_8") (pintype "passive"))
      (node (ref "R42") (pin "1") (pinfunction "1_1") (pintype "passive"))
    )
    (net (code "38") (name "Net-(D1H-C)") (class "Default")
      (node (ref "D1") (pin "13") (pinfunction "C_13") (pintype "passive"))
      (node (ref "U2") (pin "11") (pinfunction "PIO2_7_11") (pintype "bidirectional"))
    )
    (net (code "39") (name "Net-(D1I-A)") (class "Default")
      (node (ref "D1") (pin "9") (pinfunction "A_9") (pintype "passive"))
      (node (ref "R43") (pin "1") (pinfunction "1_1") (pintype "passive"))
    )
    (net (code "40") (name "Net-(D1I-C)") (class "Default")
      (node (ref "D1") (pin "12") (pinfunction "C_12") (pintype "passive"))
      (node (ref "U2") (pin "12") (pinfunction "PIO2_8_12") (pintype "bidirectional"))
    )
    (net (code "41") (name "Net-(D1J-A)") (class "Default")
      (node (ref "D1") (pin "10") (pinfunction "A_10") (pintype "passive"))
      (node (ref "R44") (pin "1") (pinfunction "1_1") (pintype "passive"))
    )
    (net (code "42") (name "Net-(D1J-C)") (class "Default")
      (node (ref "D1") (pin "11") (pinfunction "C_11") (pintype "passive"))
      (node (ref "U2") (pin "24") (pinfunction "PIO2_9_24") (pintype "bidirectional"))
    )
    (net (code "43") (name "Net-(D2-A)") (class "Default")
      (node (ref "D2") (pin "P$1") (pinfunction "A_P$1") (pintype "passive"))
      (node (ref "D5") (pin "P$1") (pinfunction "A_P$1") (pintype "passive"))
      (node (ref "J1") (pin "PWR") (pinfunction "PWR_PWR") (pintype "bidirectional"))
    )
    (net (code "44") (name "Net-(D2-C)") (class "Default")
      (node (ref "C13") (pin "1") (pinfunction "1_1") (pintype "passive"))
      (node (ref "C14") (pin "1") (pinfunction "1_1") (pintype "passive"))
      (node (ref "C22") (pin "+") (pinfunction "+_+") (pintype "passive"))
      (node (ref "D2") (pin "P$2") (pinfunction "C_P$2") (pintype "passive"))
      (node (ref "IC6") (pin "1") (pinfunction "S_1") (pintype "bidirectional"))
      (node (ref "IC6") (pin "2") (pinfunction "S_2") (pintype "bidirectional"))
      (node (ref "IC6") (pin "3") (pinfunction "S_3") (pintype "bidirectional"))
      (node (ref "U4") (pin "1") (pinfunction "CCSN_1") (pintype "bidirectional"))
      (node (ref "U4") (pin "15") (pinfunction "DCIN_15") (pintype "bidirectional"))
      (node (ref "U4") (pin "2") (pinfunction "CCSP_2") (pintype "bidirectional"))
    )
    (net (code "45") (name "Net-(D3-C)") (class "Default")
      (node (ref "D3") (pin "P$2") (pinfunction "C_P$2") (pintype "passive"))
      (node (ref "IC6") (pin "5") (pinfunction "D_5") (pintype "bidirectional"))
      (node (ref "IC6") (pin "6") (pinfunction "D_6") (pintype "bidirectional"))
      (node (ref "IC6") (pin "7") (pinfunction "D_7") (pintype "bidirectional"))
      (node (ref "IC6") (pin "8") (pinfunction "D_8") (pintype "bidirectional"))
      (node (ref "L1") (pin "1") (pinfunction "1_1") (pintype "passive"))
    )
    (net (code "46") (name "Net-(D4-C)") (class "Default")
      (node (ref "C2") (pin "1") (pinfunction "1_1") (pintype "passive"))
      (node (ref "D4") (pin "P$2") (pinfunction "C_P$2") (pintype "passive"))
      (node (ref "IC2") (pin "1") (pinfunction "PIN1_1") (pintype "bidirectional"))
      (node (ref "L2") (pin "1") (pinfunction "1_1") (pintype "passive"))
    )
    (net (code "47") (name "Net-(D6-A)") (class "Default")
      (node (ref "C23") (pin "+") (pinfunction "+_+") (pintype "passive"))
      (node (ref "C8") (pin "1") (pinfunction "1_1") (pintype "passive"))
      (node (ref "D6") (pin "P$1") (pinfunction "A_P$1") (pintype "passive"))
      (node (ref "D8") (pin "A") (pinfunction "A_A") (pintype "passive"))
      (node (ref "IC5") (pin "1") (pinfunction "S_1") (pintype "bidirectional"))
      (node (ref "IC5") (pin "2") (pinfunction "S_2") (pintype "bidirectional"))
      (node (ref "IC5") (pin "3") (pinfunction "S_3") (pintype "bidirectional"))
      (node (ref "R17") (pin "1") (pinfunction "1_1") (pintype "passive"))
      (node (ref "R19") (pin "2") (pinfunction "2_2") (pintype "passive"))
      (node (ref "SJ2") (pin "1") (pinfunction "1_1") (pintype "passive"))
      (node (ref "TP8") (pin "TP") (pinfunction "PP_TP") (pintype "input"))
      (node (ref "U4") (pin "10") (pinfunction "BATT_10") (pintype "bidirectional"))
    )
    (net (code "48") (name "Net-(IC1A-+IN)") (class "Default")
      (node (ref "IC1") (pin "3") (pinfunction "+IN_3") (pintype "input"))
      (node (ref "R7") (pin "2") (pinfunction "2_2") (pintype "passive"))
      (node (ref "R9") (pin "2") (pinfunction "2_2") (pintype "passive"))
    )
    (net (code "49") (name "Net-(IC1A--IN)") (class "Default")
      (node (ref "IC1") (pin "2") (pinfunction "-IN_2") (pintype "input"))
      (node (ref "R3") (pin "2") (pinfunction "2_2") (pintype "passive"))
      (node (ref "R8") (pin "1") (pinfunction "1_1") (pintype "passive"))
    )
    (net (code "50") (name "Net-(IC1A-OUT)") (class "Default")
      (node (ref "IC1") (pin "1") (pinfunction "OUT_1") (pintype "output"))
      (node (ref "IC1") (pin "5") (pinfunction "+IN_5") (pintype "input"))
      (node (ref "R8") (pin "2") (pinfunction "2_2") (pintype "passive"))
    )
    (net (code "51") (name "Net-(IC1B--IN)") (class "Default")
      (node (ref "IC1") (pin "6") (pinfunction "-IN_6") (pintype "input"))
      (node (ref "R10") (pin "2") (pinfunction "2_2") (pintype "passive"))
      (node (ref "R11") (pin "1") (pinfunction "1_1") (pintype "passive"))
    )
    (net (code "52") (name "Net-(IC1B-OUT)") (class "Default")
      (node (ref "IC1") (pin "7") (pinfunction "OUT_7") (pintype "output"))
      (node (ref "R11") (pin "2") (pinfunction "2_2") (pintype "passive"))
      (node (ref "R51") (pin "1") (pinfunction "1_1") (pintype "passive"))
    )
    (net (code "53") (name "Net-(IC2-PIN3)") (class "Default")
      (node (ref "C6") (pin "1") (pinfunction "1_1") (pintype "passive"))
      (node (ref "IC2") (pin "3") (pinfunction "PIN3_3") (pintype "bidirectional"))
    )
    (net (code "54") (name "Net-(IC2-PIN4)") (class "Default")
      (node (ref "IC2") (pin "4") (pinfunction "PIN4_4") (pintype "bidirectional"))
      (node (ref "R1") (pin "1") (pinfunction "1_1") (pintype "passive"))
      (node (ref "R2") (pin "2") (pinfunction "2_2") (pintype "passive"))
    )
    (net (code "55") (name "Net-(IC2-PIN7)") (class "Default")
      (node (ref "C2") (pin "2") (pinfunction "2_2") (pintype "passive"))
      (node (ref "IC2") (pin "7") (pinfunction "PIN7_7") (pintype "bidirectional"))
    )
    (net (code "56") (name "Net-(IC4-D-Pad5)") (class "Default")
      (node (ref "IC4") (pin "5") (pinfunction "D_5") (pintype "bidirectional"))
      (node (ref "IC4") (pin "6") (pinfunction "D_6") (pintype "bidirectional"))
      (node (ref "IC4") (pin "7") (pinfunction "D_7") (pintype "bidirectional"))
      (node (ref "IC4") (pin "8") (pinfunction "D_8") (pintype "bidirectional"))
      (node (ref "IC5") (pin "5") (pinfunction "D_5") (pintype "bidirectional"))
      (node (ref "IC5") (pin "6") (pinfunction "D_6") (pintype "bidirectional"))
      (node (ref "IC5") (pin "7") (pinfunction "D_7") (pintype "bidirectional"))
      (node (ref "IC5") (pin "8") (pinfunction "D_8") (pintype "bidirectional"))
    )
    (net (code "57") (name "Net-(IC4-G)") (class "Default")
      (node (ref "IC4") (pin "4") (pinfunction "G_4") (pintype "bidirectional"))
      (node (ref "R18") (pin "2") (pinfunction "2_2") (pintype "passive"))
      (node (ref "R31") (pin "2") (pinfunction "2_2") (pintype "passive"))
    )
    (net (code "58") (name "Net-(IC5-G)") (class "Default")
      (node (ref "IC5") (pin "4") (pinfunction "G_4") (pintype "bidirectional"))
      (node (ref "R17") (pin "2") (pinfunction "2_2") (pintype "passive"))
      (node (ref "R30") (pin "1") (pinfunction "1_1") (pintype "passive"))
    )
    (net (code "59") (name "Net-(IC6-G)") (class "Default")
      (node (ref "IC6") (pin "4") (pinfunction "G_4") (pintype "bidirectional"))
      (node (ref "U4") (pin "14") (pinfunction "EXT_14") (pintype "bidirectional"))
    )
    (net (code "60") (name "Net-(Q1-D)") (class "Default")
      (node (ref "Q1") (pin "3") (pinfunction "D_3") (pintype "passive"))
      (node (ref "R32") (pin "2") (pinfunction "2_2") (pintype "passive"))
    )
    (net (code "61") (name "Net-(Q2-D)") (class "Default")
      (node (ref "Q2") (pin "3") (pinfunction "D_3") (pintype "passive"))
      (node (ref "R24") (pin "2") (pinfunction "2_2") (pintype "passive"))
      (node (ref "R32") (pin "1") (pinfunction "1_1") (pintype "passive"))
      (node (ref "TP7") (pin "TP") (pinfunction "PP_TP") (pintype "input"))
      (node (ref "U4") (pin "6") (pinfunction "ICHG/EN_6") (pintype "bidirectional"))
    )
    (net (code "62") (name "Net-(R15-Pad2)") (class "Default")
      (node (ref "R15") (pin "2") (pinfunction "2_2") (pintype "passive"))
      (node (ref "SJ1") (pin "2") (pinfunction "2_2") (pintype "passive"))
    )
    (net (code "63") (name "Net-(TP1-PP)") (class "Default")
      (node (ref "D7") (pin "A") (pinfunction "A_A") (pintype "passive"))
      (node (ref "IC4") (pin "1") (pinfunction "S_1") (pintype "bidirectional"))
      (node (ref "IC4") (pin "2") (pinfunction "S_2") (pintype "bidirectional"))
      (node (ref "IC4") (pin "3") (pinfunction "S_3") (pintype "bidirectional"))
      (node (ref "R14") (pin "1") (pinfunction "1_1") (pintype "passive"))
      (node (ref "R18") (pin "1") (pinfunction "1_1") (pintype "passive"))
      (node (ref "SJ2") (pin "2") (pinfunction "2_2") (pintype "passive"))
      (node (ref "TP1") (pin "TP") (pinfunction "PP_TP") (pintype "input"))
      (node (ref "X4") (pin "P$1") (pinfunction "1_P$1") (pintype "passive"))
    )
    (net (code "64") (name "Net-(TP2-PP)") (class "Default")
      (node (ref "R13") (pin "1") (pinfunction "1_1") (pintype "passive"))
      (node (ref "TP2") (pin "TP") (pinfunction "PP_TP") (pintype "input"))
      (node (ref "X4") (pin "P$2") (pinfunction "1_P$2") (pintype "passive"))
    )
    (net (code "65") (name "Net-(TP3-PP)") (class "Default")
      (node (ref "R12") (pin "1") (pinfunction "1_1") (pintype "passive"))
      (node (ref "TP3") (pin "TP") (pinfunction "PP_TP") (pintype "input"))
      (node (ref "X4") (pin "P$3") (pinfunction "1_P$3") (pintype "passive"))
    )
    (net (code "66") (name "Net-(TP4-PP)") (class "Default")
      (node (ref "R21") (pin "2") (pinfunction "2_2") (pintype "passive"))
      (node (ref "R6") (pin "1") (pinfunction "1_1") (pintype "passive"))
      (node (ref "TP4") (pin "TP") (pinfunction "PP_TP") (pintype "input"))
      (node (ref "U3") (pin "8") (pinfunction "SR1_8") (pintype "bidirectional"))
      (node (ref "X4") (pin "P$4") (pinfunction "1_P$4") (pintype "passive"))
    )
    (net (code "67") (name "Net-(U2-RESET{slash}PIO0_0)") (class "Default")
      (node (ref "R45") (pin "2") (pinfunction "2_2") (pintype "passive"))
      (node (ref "U2") (pin "3") (pinfunction "RESET/PIO0_0_3") (pintype "bidirectional"))
    )
    (net (code "68") (name "Net-(U2-SWCLK{slash}PIO0_10{slash}SCK0{slash}CT16B0_MAT2)") (class "Default")
      (node (ref "SWD") (pin "2") (pinfunction "2_2") (pintype "passive"))
      (node (ref "U2") (pin "29") (pinfunction "SWCLK/PIO0_10/SCK0/CT16B0_MAT2_29") (pintype "bidirectional"))
    )
    (net (code "69") (name "Net-(U2-SWDIO{slash}PIO1_3{slash}AD4{slash}CT32B1_MAT2)") (class "Default")
      (node (ref "SWD") (pin "3") (pinfunction "3_3") (pintype "passive"))
      (node (ref "U2") (pin "39") (pinfunction "SWDIO/PIO1_3/AD4/CT32B1_MAT2_39") (pintype "bidirectional"))
    )
    (net (code "70") (name "Net-(U2-XTALIN)") (class "Default")
      (node (ref "C28") (pin "1") (pinfunction "1_1") (pintype "passive"))
      (node (ref "U2") (pin "6") (pinfunction "XTALIN_6") (pintype "input"))
      (node (ref "Y1") (pin "1") (pinfunction "1_1") (pintype "passive"))
    )
    (net (code "71") (name "Net-(U2-XTALOUT)") (class "Default")
      (node (ref "C27") (pin "1") (pinfunction "1_1") (pintype "passive"))
      (node (ref "U2") (pin "7") (pinfunction "XTALOUT_7") (pintype "output"))
      (node (ref "Y1") (pin "2") (pinfunction "2_2") (pintype "passive"))
    )
    (net (code "72") (name "Net-(U3-BAT)") (class "Default")
      (node (ref "C25") (pin "2") (pinfunction "2_2") (pintype "passive"))
      (node (ref "D7") (pin "C") (pinfunction "C_C") (pintype "passive"))
      (node (ref "U3") (pin "1") (pinfunction "BAT_1") (pintype "bidirectional"))
    )
    (net (code "73") (name "Net-(U3-CELL)") (class "Default")
      (node (ref "R16") (pin "2") (pinfunction "2_2") (pintype "passive"))
      (node (ref "U3") (pin "11") (pinfunction "CELL_11") (pintype "bidirectional"))
    )
    (net (code "74") (name "Net-(U3-CHG)") (class "Default")
      (node (ref "R30") (pin "2") (pinfunction "2_2") (pintype "passive"))
      (node (ref "U3") (pin "20") (pinfunction "CHG_20") (pintype "bidirectional"))
    )
    (net (code "75") (name "Net-(U3-DSG)") (class "Default")
      (node (ref "R31") (pin "1") (pinfunction "1_1") (pintype "passive"))
      (node (ref "U3") (pin "2") (pinfunction "DSG_2") (pintype "bidirectional"))
    )
    (net (code "76") (name "Net-(U3-PACK)") (class "Default")
      (node (ref "C26") (pin "2") (pinfunction "2_2") (pintype "passive"))
      (node (ref "D8") (pin "C") (pinfunction "C_C") (pintype "passive"))
      (node (ref "SJ1") (pin "1") (pinfunction "1_1") (pintype "passive"))
      (node (ref "U3") (pin "22") (pinfunction "PACK_22") (pintype "bidirectional"))
    )
    (net (code "77") (name "Net-(U3-PMS)") (class "Default")
      (node (ref "R15") (pin "1") (pinfunction "1_1") (pintype "passive"))
      (node (ref "U3") (pin "23") (pinfunction "PMS_23") (pintype "bidirectional"))
    )
    (net (code "78") (name "Net-(U3-SLEEP)") (class "Default")
      (node (ref "R22") (pin "1") (pinfunction "1_1") (pintype "passive"))
      (node (ref "U3") (pin "19") (pinfunction "SLEEP_19") (pintype "bidirectional"))
    )
    (net (code "79") (name "Net-(U3-VC1)") (class "Default")
      (node (ref "C15") (pin "2") (pinfunction "2_2") (pintype "passive"))
      (node (ref "R14") (pin "2") (pinfunction "2_2") (pintype "passive"))
      (node (ref "U3") (pin "3") (pinfunction "VC1_3") (pintype "bidirectional"))
      (node (ref "U3") (pin "4") (pinfunction "VC2_4") (pintype "bidirectional"))
    )
    (net (code "80") (name "Net-(U3-VC3)") (class "Default")
      (node (ref "C12") (pin "2") (pinfunction "2_2") (pintype "passive"))
      (node (ref "R13") (pin "2") (pinfunction "2_2") (pintype "passive"))
      (node (ref "U3") (pin "5") (pinfunction "VC3_5") (pintype "bidirectional"))
    )
    (net (code "81") (name "Net-(U3-VC4)") (class "Default")
      (node (ref "C11") (pin "2") (pinfunction "2_2") (pintype "passive"))
      (node (ref "R12") (pin "2") (pinfunction "2_2") (pintype "passive"))
      (node (ref "U3") (pin "6") (pinfunction "VC4_6") (pintype "bidirectional"))
    )
    (net (code "82") (name "Net-(U3-VC5)") (class "Default")
      (node (ref "C10") (pin "2") (pinfunction "2_2") (pintype "passive"))
      (node (ref "R6") (pin "2") (pinfunction "2_2") (pintype "passive"))
      (node (ref "U3") (pin "7") (pinfunction "VC5_7") (pintype "bidirectional"))
    )
    (net (code "83") (name "Net-(U4-CCI)") (class "Default")
      (node (ref "C19") (pin "1") (pinfunction "1_1") (pintype "passive"))
      (node (ref "U4") (pin "5") (pinfunction "CCI_5") (pintype "bidirectional"))
    )
    (net (code "84") (name "Net-(U4-CCS)") (class "Default")
      (node (ref "C20") (pin "1") (pinfunction "1_1") (pintype "passive"))
      (node (ref "U4") (pin "3") (pinfunction "CCS_3") (pintype "bidirectional"))
    )
    (net (code "85") (name "Net-(U4-CCV)") (class "Default")
      (node (ref "C24") (pin "1") (pinfunction "1_1") (pintype "passive"))
      (node (ref "R25") (pin "1") (pinfunction "1_1") (pintype "passive"))
      (node (ref "U4") (pin "4") (pinfunction "CCV_4") (pintype "bidirectional"))
    )
    (net (code "86") (name "Net-(U4-CSB)") (class "Default")
      (node (ref "L1") (pin "2") (pinfunction "2_2") (pintype "passive"))
      (node (ref "R19") (pin "1") (pinfunction "1_1") (pintype "passive"))
      (node (ref "U4") (pin "11") (pinfunction "CSB_11") (pintype "bidirectional"))
    )
    (net (code "87") (name "Net-(U4-REF)") (class "Default")
      (node (ref "C9") (pin "1") (pinfunction "1_1") (pintype "passive"))
      (node (ref "R20") (pin "2") (pinfunction "2_2") (pintype "passive"))
      (node (ref "R24") (pin "1") (pinfunction "1_1") (pintype "passive"))
      (node (ref "U4") (pin "9") (pinfunction "REF_9") (pintype "bidirectional"))
    )
    (net (code "88") (name "Net-(U4-VADJ)") (class "Default")
      (node (ref "R20") (pin "1") (pinfunction "1_1") (pintype "passive"))
      (node (ref "R23") (pin "2") (pinfunction "2_2") (pintype "passive"))
      (node (ref "U4") (pin "8") (pinfunction "VADJ_8") (pintype "bidirectional"))
    )
    (net (code "89") (name "Net-(U4-VH)") (class "Default")
      (node (ref "C14") (pin "2") (pinfunction "2_2") (pintype "passive"))
      (node (ref "U4") (pin "13") (pinfunction "VH_13") (pintype "bidirectional"))
    )
    (net (code "90") (name "Net-(U4-VL)") (class "Default")
      (node (ref "C18") (pin "1") (pinfunction "1_1") (pintype "passive"))
      (node (ref "U4") (pin "16") (pinfunction "VL_16") (pintype "bidirectional"))
    )
    (net (code "91") (name "unconnected-(B1-S1-PadB')") (class "Default")
      (node (ref "B1") (pin "B'") (pinfunction "S1_B'") (pintype "passive"))
    )
    (net (code "92") (name "unconnected-(CN3-PadD+)") (class "Default")
      (node (ref "CN3") (pin "D+") (pinfunction "D+_D+") (pintype "bidirectional"))
    )
    (net (code "93") (name "unconnected-(CN3-PadD-)") (class "Default")
      (node (ref "CN3") (pin "D-") (pinfunction "D-_D-") (pintype "bidirectional"))
    )
    (net (code "94") (name "unconnected-(U2-PIO0_2{slash}SSEL0{slash}CT16B0_CAP0-Pad10)") (class "Default")
      (node (ref "U2") (pin "10") (pinfunction "PIO0_2/SSEL0/CT16B0_CAP0_10") (pintype "bidirectional"))
    )
    (net (code "95") (name "unconnected-(U2-PIO0_3-Pad14)") (class "Default")
      (node (ref "U2") (pin "14") (pinfunction "PIO0_3_14") (pintype "bidirectional"))
    )
    (net (code "96") (name "unconnected-(U2-PIO0_6{slash}SCK0-Pad22)") (class "Default")
      (node (ref "U2") (pin "22") (pinfunction "PIO0_6/SCK0_22") (pintype "bidirectional"))
    )
    (net (code "97") (name "unconnected-(U2-PIO0_7{slash}CTS-Pad23)") (class "Default")
      (node (ref "U2") (pin "23") (pinfunction "PIO0_7/CTS_23") (pintype "bidirectional"))
    )
    (net (code "98") (name "unconnected-(U2-PIO0_8{slash}MISO0{slash}CT16B0_MAT0-Pad27)") (class "Default")
      (node (ref "U2") (pin "27") (pinfunction "PIO0_8/MISO0/CT16B0_MAT0_27") (pintype "bidirectional"))
    )
    (net (code "99") (name "unconnected-(U2-PIO0_9{slash}MOSI0{slash}CT16B0_MAT1-Pad28)") (class "Default")
      (node (ref "U2") (pin "28") (pinfunction "PIO0_9/MOSI0/CT16B0_MAT1_28") (pintype "bidirectional"))
    )
    (net (code "100") (name "unconnected-(U2-PIO1_4{slash}AD5{slash}CT32B1_MAT3{slash}WAKEUP-Pad40)") (class "Default")
      (node (ref "U2") (pin "40") (pinfunction "PIO1_4/AD5/CT32B1_MAT3/WAKEUP_40") (pintype "bidirectional"))
    )
    (net (code "101") (name "unconnected-(U2-PIO1_5{slash}RTS{slash}CT32B0_CAP0-Pad45)") (class "Default")
      (node (ref "U2") (pin "45") (pinfunction "PIO1_5/RTS/CT32B0_CAP0_45") (pintype "bidirectional"))
    )
    (net (code "102") (name "unconnected-(U2-PIO1_6{slash}RXD{slash}CT32B0_MAT0-Pad46)") (class "Default")
      (node (ref "U2") (pin "46") (pinfunction "PIO1_6/RXD/CT32B0_MAT0_46") (pintype "bidirectional"))
    )
    (net (code "103") (name "unconnected-(U2-PIO1_7{slash}TXD{slash}CT32B0_MAT1-Pad47)") (class "Default")
      (node (ref "U2") (pin "47") (pinfunction "PIO1_7/TXD/CT32B0_MAT1_47") (pintype "bidirectional"))
    )
    (net (code "104") (name "unconnected-(U2-PIO1_9{slash}CT16B1_MAT0-Pad17)") (class "Default")
      (node (ref "U2") (pin "17") (pinfunction "PIO1_9/CT16B1_MAT0_17") (pintype "bidirectional"))
    )
    (net (code "105") (name "unconnected-(U2-PIO1_10{slash}AD6{slash}CT16B1_MAT1-Pad30)") (class "Default")
      (node (ref "U2") (pin "30") (pinfunction "PIO1_10/AD6/CT16B1_MAT1_30") (pintype "bidirectional"))
    )
    (net (code "106") (name "unconnected-(U2-PIO2_10-Pad25)") (class "Default")
      (node (ref "U2") (pin "25") (pinfunction "PIO2_10_25") (pintype "bidirectional"))
    )
    (net (code "107") (name "unconnected-(U2-PIO2_11{slash}SCK0-Pad31)") (class "Default")
      (node (ref "U2") (pin "31") (pinfunction "PIO2_11/SCK0_31") (pintype "bidirectional"))
    )
    (net (code "108") (name "unconnected-(U2-PIO3_3{slash}RI-Pad48)") (class "Default")
      (node (ref "U2") (pin "48") (pinfunction "PIO3_3/RI_48") (pintype "bidirectional"))
    )
    (net (code "109") (name "unconnected-(U2-PIO3_4-Pad18)") (class "Default")
      (node (ref "U2") (pin "18") (pinfunction "PIO3_4_18") (pintype "bidirectional"))
    )
    (net (code "110") (name "unconnected-(U2-PIO3_5-Pad21)") (class "Default")
      (node (ref "U2") (pin "21") (pinfunction "PIO3_5_21") (pintype "bidirectional"))
    )
    (net (code "111") (name "unconnected-(U2-TRST{slash}PIO1_2{slash}AD3{slash}CT32B1_MAT1-Pad35)") (class "Default")
      (node (ref "U2") (pin "35") (pinfunction "TRST/PIO1_2/AD3/CT32B1_MAT1_35") (pintype "bidirectional"))
    )
    (net (code "112") (name "unconnected-(U3-OD-Pad24)") (class "Default")
      (node (ref "U3") (pin "24") (pinfunction "OD_24") (pintype "bidirectional"))
    )
    (net (code "113") (name "unconnected-(U3-TOUT-Pad17)") (class "Default")
      (node (ref "U3") (pin "17") (pinfunction "TOUT_17") (pintype "bidirectional"))
    )
    (net (code "114") (name "unconnected-(U3-ZVCHG-Pad21)") (class "Default")
      (node (ref "U3") (pin "21") (pinfunction "ZVCHG_21") (pintype "bidirectional"))
    )
    (net (code "115") (name "unconnected-(U4-IOUT-Pad7)") (class "Default")
      (node (ref "U4") (pin "7") (pinfunction "IOUT_7") (pintype "bidirectional"))
    )
  )
)
